# TLine.net
KiCad netlist of a schematic drawn in Altium Designer
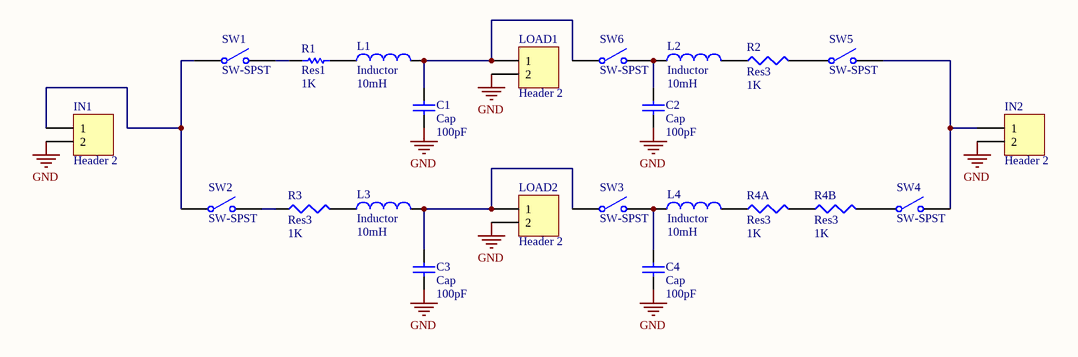
[diagram p0: TLine.SchDoc]

(export (version "E")
  (design (tool "Eeschema 10.0.6"))
  (components
    (comp (ref "C1")
      (value "Cap")
      (footprint "capcap")
      (description "Capacitor")
      (fields (field (name "ALTIUM_VALUE") "100pF") (field (name "PUBLISHER") "Altium Limited"))
      (libsource (lib "Miscellaneous Devices") (part "Cap"))
    )
    (comp (ref "C2")
      (value "Cap")
      (footprint "CapBig")
      (description "Capacitor")
      (fields (field (name "ALTIUM_VALUE") "100pF") (field (name "PUBLISHER") "Altium Limited"))
      (libsource (lib "Miscellaneous Devices") (part "Cap"))
    )
    (comp (ref "C3")
      (value "Cap")
      (footprint "CapBig")
      (description "Capacitor")
      (fields (field (name "ALTIUM_VALUE") "100pF") (field (name "PUBLISHER") "Altium Limited"))
      (libsource (lib "Miscellaneous Devices") (part "Cap"))
    )
    (comp (ref "C4")
      (value "Cap")
      (footprint "capcap")
      (description "Capacitor")
      (fields (field (name "ALTIUM_VALUE") "100pF") (field (name "PUBLISHER") "Altium Limited"))
      (libsource (lib "Miscellaneous Devices") (part "Cap"))
    )
    (comp (ref "IN1")
      (value "Header 2")
      (footprint "TB")
      (description "Header, 2-Pin")
      (fields (field (name "PUBLISHER") "Altium Limited"))
      (libsource (lib "Miscellaneous Connectors") (part "Header 2"))
    )
    (comp (ref "IN2")
      (value "Header 2")
      (footprint "TB")
      (description "Header, 2-Pin")
      (fields (field (name "PUBLISHER") "Altium Limited"))
      (libsource (lib "Miscellaneous Connectors") (part "Header 2"))
    )
    (comp (ref "L1")
      (value "Inductor")
      (footprint "Inductor1")
      (fields (field (name "ALTIUM_VALUE") "10mH") (field (name "PUBLISHER") "Altium Limited"))
      (libsource (lib "Miscellaneous Devices") (part "Inductor"))
    )
    (comp (ref "L2")
      (value "Inductor")
      (footprint "Inductor1")
      (fields (field (name "ALTIUM_VALUE") "10mH") (field (name "PUBLISHER") "Altium Limited"))
      (libsource (lib "Miscellaneous Devices") (part "Inductor"))
    )
    (comp (ref "L3")
      (value "Inductor")
      (footprint "Inductor1")
      (fields (field (name "ALTIUM_VALUE") "10mH") (field (name "PUBLISHER") "Altium Limited"))
      (libsource (lib "Miscellaneous Devices") (part "Inductor"))
    )
    (comp (ref "L4")
      (value "Inductor")
      (footprint "Inductor4")
      (fields (field (name "ALTIUM_VALUE") "10mH") (field (name "PUBLISHER") "Altium Limited"))
      (libsource (lib "Miscellaneous Devices") (part "Inductor"))
    )
    (comp (ref "LOAD1")
      (value "Header 2")
      (footprint "CAPhoriz")
      (description "Header, 2-Pin")
      (fields (field (name "PUBLISHER") "Altium Limited"))
      (libsource (lib "Miscellaneous Connectors") (part "Header 2"))
    )
    (comp (ref "LOAD2")
      (value "Header 2")
      (footprint "CAPhoriz")
      (description "Header, 2-Pin")
      (fields (field (name "PUBLISHER") "Altium Limited"))
      (libsource (lib "Miscellaneous Connectors") (part "Header 2"))
    )
    (comp (ref "R1")
      (value "Res1")
      (footprint "Resistor1")
      (description "Resistor")
      (fields (field (name "ALTIUM_VALUE") "1K") (field (name "PUBLISHER") "Altium Limited"))
      (libsource (lib "Miscellaneous Devices") (part "Res1"))
    )
    (comp (ref "R2")
      (value "Res3")
      (footprint "Resistor3")
      (description "Resistor")
      (fields (field (name "ALTIUM_VALUE") "1K") (field (name "PUBLISHER") "Altium Limited"))
      (libsource (lib "Miscellaneous Devices") (part "Res3"))
    )
    (comp (ref "R3")
      (value "Res3")
      (footprint "Resistor3")
      (description "Resistor")
      (fields (field (name "ALTIUM_VALUE") "1K") (field (name "PUBLISHER") "Altium Limited"))
      (libsource (lib "Miscellaneous Devices") (part "Res3"))
    )
    (comp (ref "R4A")
      (value "Res3")
      (footprint "Resistor3")
      (description "Resistor")
      (fields (field (name "ALTIUM_VALUE") "1K") (field (name "PUBLISHER") "Altium Limited"))
      (libsource (lib "Miscellaneous Devices") (part "Res3"))
    )
    (comp (ref "R4B")
      (value "Res3")
      (footprint "Resistor3")
      (description "Resistor")
      (fields (field (name "ALTIUM_VALUE") "1K") (field (name "PUBLISHER") "Altium Limited"))
      (libsource (lib "Miscellaneous Devices") (part "Res3"))
    )
    (comp (ref "SW1")
      (value "SW-SPST")
      (footprint "Switch")
      (description "Single-Pole, Single-Throw Switch")
      (fields (field (name "PUBLISHER") "Altium Limited"))
      (libsource (lib "Miscellaneous Devices") (part "SW-SPST"))
    )
    (comp (ref "SW2")
      (value "SW-SPST")
      (footprint "Switch")
      (description "Single-Pole, Single-Throw Switch")
      (fields (field (name "PUBLISHER") "Altium Limited"))
      (libsource (lib "Miscellaneous Devices") (part "SW-SPST"))
    )
    (comp (ref "SW3")
      (value "SW-SPST")
      (footprint "Switch")
      (description "Single-Pole, Single-Throw Switch")
      (fields (field (name "PUBLISHER") "Altium Limited"))
      (libsource (lib "Miscellaneous Devices") (part "SW-SPST"))
    )
    (comp (ref "SW4")
      (value "SW-SPST")
      (footprint "Switch")
      (description "Single-Pole, Single-Throw Switch")
      (fields (field (name "PUBLISHER") "Altium Limited"))
      (libsource (lib "Miscellaneous Devices") (part "SW-SPST"))
    )
    (comp (ref "SW5")
      (value "SW-SPST")
      (footprint "Switch")
      (description "Single-Pole, Single-Throw Switch")
      (fields (field (name "PUBLISHER") "Altium Limited"))
      (libsource (lib "Miscellaneous Devices") (part "SW-SPST"))
    )
    (comp (ref "SW6")
      (value "SW-SPST")
      (footprint "Switch")
      (description "Single-Pole, Single-Throw Switch")
      (fields (field (name "PUBLISHER") "Altium Limited"))
      (libsource (lib "Miscellaneous Devices") (part "SW-SPST"))
    )
  )
  (nets
    (net (code "1") (name "GND") (class "Default")
      (node (ref "C1") (pin "1") (pinfunction "1_1") (pintype "passive"))
      (node (ref "C2") (pin "1") (pinfunction "1_1") (pintype "passive"))
      (node (ref "C3") (pin "1") (pinfunction "1_1") (pintype "passive"))
      (node (ref "C4") (pin "1") (pinfunction "1_1") (pintype "passive"))
      (node (ref "IN1") (pin "2") (pinfunction "2_2") (pintype "passive"))
      (node (ref "IN2") (pin "2") (pinfunction "2_2") (pintype "passive"))
      (node (ref "LOAD1") (pin "2") (pinfunction "2_2") (pintype "passive"))
      (node (ref "LOAD2") (pin "2") (pinfunction "2_2") (pintype "passive"))
    )
    (net (code "2") (name "Net-(L1-Pad1)") (class "Default")
      (node (ref "L1") (pin "1") (pinfunction "1_1") (pintype "passive"))
      (node (ref "R1") (pin "2") (pinfunction "2_2") (pintype "passive"))
    )
    (net (code "3") (name "Net-(L2-Pad2)") (class "Default")
      (node (ref "L2") (pin "2") (pinfunction "2_2") (pintype "passive"))
      (node (ref "R2") (pin "1") (pinfunction "1_1") (pintype "passive"))
    )
    (net (code "4") (name "Net-(L3-Pad1)") (class "Default")
      (node (ref "L3") (pin "1") (pinfunction "1_1") (pintype "passive"))
      (node (ref "R3") (pin "2") (pinfunction "2_2") (pintype "passive"))
    )
    (net (code "5") (name "Net-(L4-Pad2)") (class "Default")
      (node (ref "L4") (pin "2") (pinfunction "2_2") (pintype "passive"))
      (node (ref "R4A") (pin "1") (pinfunction "1_1") (pintype "passive"))
    )
    (net (code "6") (name "Net-(R4A-Pad2)") (class "Default")
      (node (ref "R4A") (pin "2") (pinfunction "2_2") (pintype "passive"))
      (node (ref "R4B") (pin "1") (pinfunction "1_1") (pintype "passive"))
    )
    (net (code "7") (name "Net-(SW1-COMMON)") (class "Default")
      (node (ref "IN1") (pin "1") (pinfunction "1_1") (pintype "passive"))
      (node (ref "SW1") (pin "1") (pinfunction "COMMON_1") (pintype "passive"))
      (node (ref "SW2") (pin "1") (pinfunction "COMMON_1") (pintype "passive"))
    )
    (net (code "8") (name "Net-(SW1-NO)") (class "Default")
      (node (ref "R1") (pin "1") (pinfunction "1_1") (pintype "passive"))
      (node (ref "SW1") (pin "2") (pinfunction "NO_2") (pintype "passive"))
    )
    (net (code "9") (name "Net-(SW2-NO)") (class "Default")
      (node (ref "R3") (pin "1") (pinfunction "1_1") (pintype "passive"))
      (node (ref "SW2") (pin "2") (pinfunction "NO_2") (pintype "passive"))
    )
    (net (code "10") (name "Net-(SW3-COMMON)") (class "Default")
      (node (ref "C3") (pin "2") (pinfunction "2_2") (pintype "passive"))
      (node (ref "L3") (pin "2") (pinfunction "2_2") (pintype "passive"))
      (node (ref "LOAD2") (pin "1") (pinfunction "1_1") (pintype "passive"))
      (node (ref "SW3") (pin "1") (pinfunction "COMMON_1") (pintype "passive"))
    )
    (net (code "11") (name "Net-(SW3-NO)") (class "Default")
      (node (ref "C4") (pin "2") (pinfunction "2_2") (pintype "passive"))
      (node (ref "L4") (pin "1") (pinfunction "1_1") (pintype "passive"))
      (node (ref "SW3") (pin "2") (pinfunction "NO_2") (pintype "passive"))
    )
    (net (code "12") (name "Net-(SW4-COMMON)") (class "Default")
      (node (ref "R4B") (pin "2") (pinfunction "2_2") (pintype "passive"))
      (node (ref "SW4") (pin "1") (pinfunction "COMMON_1") (pintype "passive"))
    )
    (net (code "13") (name "Net-(SW4-NO)") (class "Default")
      (node (ref "IN2") (pin "1") (pinfunction "1_1") (pintype "passive"))
      (node (ref "SW4") (pin "2") (pinfunction "NO_2") (pintype "passive"))
      (node (ref "SW5") (pin "2") (pinfunction "NO_2") (pintype "passive"))
    )
    (net (code "14") (name "Net-(SW5-COMMON)") (class "Default")
      (node (ref "R2") (pin "2") (pinfunction "2_2") (pintype "passive"))
      (node (ref "SW5") (pin "1") (pinfunction "COMMON_1") (pintype "passive"))
    )
    (net (code "15") (name "Net-(SW6-COMMON)") (class "Default")
      (node (ref "C1") (pin "2") (pinfunction "2_2") (pintype "passive"))
      (node (ref "L1") (pin "2") (pinfunction "2_2") (pintype "passive"))
      (node (ref "LOAD1") (pin "1") (pinfunction "1_1") (pintype "passive"))
      (node (ref "SW6") (pin "1") (pinfunction "COMMON_1") (pintype "passive"))
    )
    (net (code "16") (name "Net-(SW6-NO)") (class "Default")
      (node (ref "C2") (pin "2") (pinfunction "2_2") (pintype "passive"))
      (node (ref "L2") (pin "1") (pinfunction "1_1") (pintype "passive"))
      (node (ref "SW6") (pin "2") (pinfunction "NO_2") (pintype "passive"))
    )
  )
)
